# Y-babies_ATtiny84.net
KiCad netlist of a schematic drawn in EAGLE
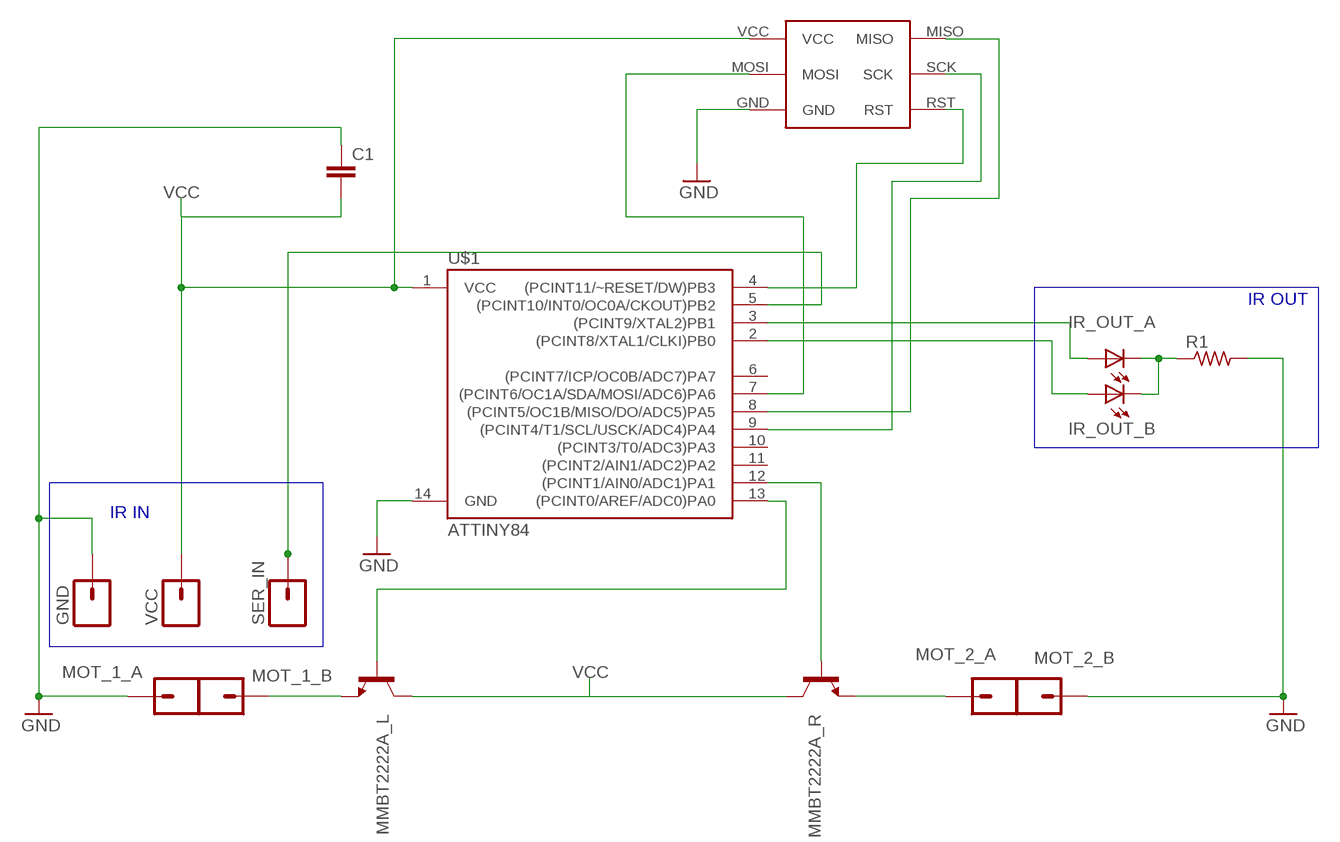
[diagram p0: schematic, sheet 1]

(export (version "E")
  (design (tool "Eeschema 10.0.6"))
  (components
    (comp (ref "C1")
      (value "CAPSMD")
      (footprint "eagle-import:GRM43D")
      (libsource (lib "eagle-import") (part "CAPSMD"))
    )
    (comp (ref "GND")
      (value "M01PTH")
      (footprint "eagle-import:1X01")
      (libsource (lib "eagle-import") (part "M01PTH"))
    )
    (comp (ref "IR_OUT_A")
      (value "LED3MM")
      (footprint "eagle-import:LED3MM")
      (libsource (lib "eagle-import") (part "LED3MM"))
    )
    (comp (ref "IR_OUT_B")
      (value "LED3MM")
      (footprint "eagle-import:LED3MM")
      (libsource (lib "eagle-import") (part "LED3MM"))
    )
    (comp (ref "MMBT2222A_L")
      (value "TRANSISTOR_NPNSOT23")
      (footprint "eagle-import:SOT23")
      (libsource (lib "eagle-import") (part "TRANSISTOR_NPNSOT23"))
    )
    (comp (ref "MMBT2222A_R")
      (value "TRANSISTOR_NPNSOT23")
      (footprint "eagle-import:SOT23")
      (libsource (lib "eagle-import") (part "TRANSISTOR_NPNSOT23"))
    )
    (comp (ref "MOT_1_A")
      (value "M01SMD-4.5X1.5")
      (footprint "eagle-import:PAD-1.5X4.5")
      (libsource (lib "eagle-import") (part "M01SMD-4.5X1.5"))
    )
    (comp (ref "MOT_1_B")
      (value "M01SMD-4.5X1.5")
      (footprint "eagle-import:PAD-1.5X4.5")
      (libsource (lib "eagle-import") (part "M01SMD-4.5X1.5"))
    )
    (comp (ref "MOT_2_A")
      (value "M01SMD-4.5X1.5")
      (footprint "eagle-import:PAD-1.5X4.5")
      (libsource (lib "eagle-import") (part "M01SMD-4.5X1.5"))
    )
    (comp (ref "MOT_2_B")
      (value "M01SMD-4.5X1.5")
      (footprint "eagle-import:PAD-1.5X4.5")
      (libsource (lib "eagle-import") (part "M01SMD-4.5X1.5"))
    )
    (comp (ref "R1")
      (value "R-US_R0805W")
      (footprint "eagle-import:R0805W")
      (libsource (lib "eagle-import") (part "R-US_R0805W"))
    )
    (comp (ref "SER_IN")
      (value "M01PTH")
      (footprint "eagle-import:1X01")
      (libsource (lib "eagle-import") (part "M01PTH"))
    )
    (comp (ref "U$1")
      (value "ATTINY84")
      (footprint "eagle-import:SO14")
      (libsource (lib "eagle-import") (part "ATTINY84"))
    )
    (comp (ref "U$2")
      (value "POGO_PIN_SPI_PAD")
      (footprint "eagle-import:POGO_PIN_SPI_PAD")
      (libsource (lib "eagle-import") (part "POGO_PIN_SPI_PAD"))
    )
    (comp (ref "VCC")
      (value "M01PTH")
      (footprint "eagle-import:1X01")
      (libsource (lib "eagle-import") (part "M01PTH"))
    )
  )
  (nets
    (net (code "1") (name "/VCC") (class "Default")
      (node (ref "C1") (pin "C") (pinfunction "2_C") (pintype "passive"))
      (node (ref "MMBT2222A_L") (pin "3") (pinfunction "C_3") (pintype "passive"))
      (node (ref "MMBT2222A_R") (pin "3") (pinfunction "C_3") (pintype "passive"))
      (node (ref "U$1") (pin "1") (pinfunction "VCC_1") (pintype "bidirectional"))
      (node (ref "U$2") (pin "VCC") (pinfunction "VCC_VCC") (pintype "bidirectional"))
      (node (ref "VCC") (pin "1") (pinfunction "1_1") (pintype "passive"))
    )
    (net (code "2") (name "GND") (class "Default")
      (node (ref "C1") (pin "A") (pinfunction "1_A") (pintype "passive"))
      (node (ref "GND") (pin "1") (pinfunction "1_1") (pintype "passive"))
      (node (ref "MOT_1_A") (pin "P$1") (pinfunction "1_P$1") (pintype "passive"))
      (node (ref "MOT_2_B") (pin "P$1") (pinfunction "1_P$1") (pintype "passive"))
      (node (ref "R1") (pin "2") (pinfunction "2_2") (pintype "passive"))
      (node (ref "U$1") (pin "14") (pinfunction "GND_14") (pintype "bidirectional"))
      (node (ref "U$2") (pin "GND") (pinfunction "GND_GND") (pintype "bidirectional"))
    )
    (net (code "3") (name "Net-(IR_OUT_A-C)") (class "Default")
      (node (ref "IR_OUT_A") (pin "K") (pinfunction "C_K") (pintype "passive"))
      (node (ref "IR_OUT_B") (pin "K") (pinfunction "C_K") (pintype "passive"))
      (node (ref "R1") (pin "1") (pinfunction "1_1") (pintype "passive"))
    )
    (net (code "4") (name "Net-(MMBT2222A_L-B)") (class "Default")
      (node (ref "MMBT2222A_L") (pin "1") (pinfunction "B_1") (pintype "passive"))
      (node (ref "U$1") (pin "13") (pinfunction "(PCINT0/AREF/ADC0)PA0_13") (pintype "bidirectional"))
    )
    (net (code "5") (name "Net-(MMBT2222A_L-E)") (class "Default")
      (node (ref "MMBT2222A_L") (pin "2") (pinfunction "E_2") (pintype "passive"))
      (node (ref "MOT_1_B") (pin "P$1") (pinfunction "1_P$1") (pintype "passive"))
    )
    (net (code "6") (name "Net-(MMBT2222A_R-B)") (class "Default")
      (node (ref "MMBT2222A_R") (pin "1") (pinfunction "B_1") (pintype "passive"))
      (node (ref "U$1") (pin "12") (pinfunction "(PCINT1/AIN0/ADC1)PA1_12") (pintype "bidirectional"))
    )
    (net (code "7") (name "Net-(MMBT2222A_R-E)") (class "Default")
      (node (ref "MMBT2222A_R") (pin "2") (pinfunction "E_2") (pintype "passive"))
      (node (ref "MOT_2_A") (pin "P$1") (pinfunction "1_P$1") (pintype "passive"))
    )
    (net (code "8") (name "Net-(U$1-(PCINT4{slash}T1{slash}SCL{slash}USCK{slash}ADC4)PA4)") (class "Default")
      (node (ref "U$1") (pin "9") (pinfunction "(PCINT4/T1/SCL/USCK/ADC4)PA4_9") (pintype "bidirectional"))
      (node (ref "U$2") (pin "SCK") (pinfunction "SCK_SCK") (pintype "bidirectional"))
    )
    (net (code "9") (name "Net-(U$1-(PCINT5{slash}OC1B{slash}MISO{slash}DO{slash}ADC5)PA5)") (class "Default")
      (node (ref "U$1") (pin "8") (pinfunction "(PCINT5/OC1B/MISO/DO/ADC5)PA5_8") (pintype "bidirectional"))
      (node (ref "U$2") (pin "MISO") (pinfunction "MISO_MISO") (pintype "bidirectional"))
    )
    (net (code "10") (name "Net-(U$1-(PCINT6{slash}OC1A{slash}SDA{slash}MOSI{slash}ADC6)PA6)") (class "Default")
      (node (ref "U$1") (pin "7") (pinfunction "(PCINT6/OC1A/SDA/MOSI/ADC6)PA6_7") (pintype "bidirectional"))
      (node (ref "U$2") (pin "MOSI") (pinfunction "MOSI_MOSI") (pintype "bidirectional"))
    )
    (net (code "11") (name "Net-(U$1-(PCINT8{slash}XTAL1{slash}CLKI)PB0)") (class "Default")
      (node (ref "IR_OUT_B") (pin "A") (pinfunction "A_A") (pintype "passive"))
      (node (ref "U$1") (pin "2") (pinfunction "(PCINT8/XTAL1/CLKI)PB0_2") (pintype "bidirectional"))
    )
    (net (code "12") (name "Net-(U$1-(PCINT9{slash}XTAL2)PB1)") (class "Default")
      (node (ref "IR_OUT_A") (pin "A") (pinfunction "A_A") (pintype "passive"))
      (node (ref "U$1") (pin "3") (pinfunction "(PCINT9/XTAL2)PB1_3") (pintype "bidirectional"))
    )
    (net (code "13") (name "Net-(U$1-(PCINT10{slash}INT0{slash}OC0A{slash}CKOUT)PB2)") (class "Default")
      (node (ref "SER_IN") (pin "1") (pinfunction "1_1") (pintype "passive"))
      (node (ref "U$1") (pin "5") (pinfunction "(PCINT10/INT0/OC0A/CKOUT)PB2_5") (pintype "bidirectional"))
    )
    (net (code "14") (name "Net-(U$1-(PCINT11{slash}~{RESET{slash}DW})PB3)") (class "Default")
      (node (ref "U$1") (pin "4") (pinfunction "(PCINT11/~{RESET/DW})PB3_4") (pintype "bidirectional"))
      (node (ref "U$2") (pin "RST") (pinfunction "RST_RST") (pintype "bidirectional"))
    )
    (net (code "15") (name "unconnected-(U$1-(PCINT2{slash}AIN1{slash}ADC2)PA2-Pad11)") (class "Default")
      (node (ref "U$1") (pin "11") (pinfunction "(PCINT2/AIN1/ADC2)PA2_11") (pintype "bidirectional"))
    )
    (net (code "16") (name "unconnected-(U$1-(PCINT3{slash}T0{slash}ADC3)PA3-Pad10)") (class "Default")
      (node (ref "U$1") (pin "10") (pinfunction "(PCINT3/T0/ADC3)PA3_10") (pintype "bidirectional"))
    )
    (net (code "17") (name "unconnected-(U$1-(PCINT7{slash}ICP{slash}OC0B{slash}ADC7)PA7-Pad6)") (class "Default")
      (node (ref "U$1") (pin "6") (pinfunction "(PCINT7/ICP/OC0B/ADC7)PA7_6") (pintype "bidirectional"))
    )
  )
)
